# Proiect.net
KiCad netlist of a schematic drawn in EAGLE
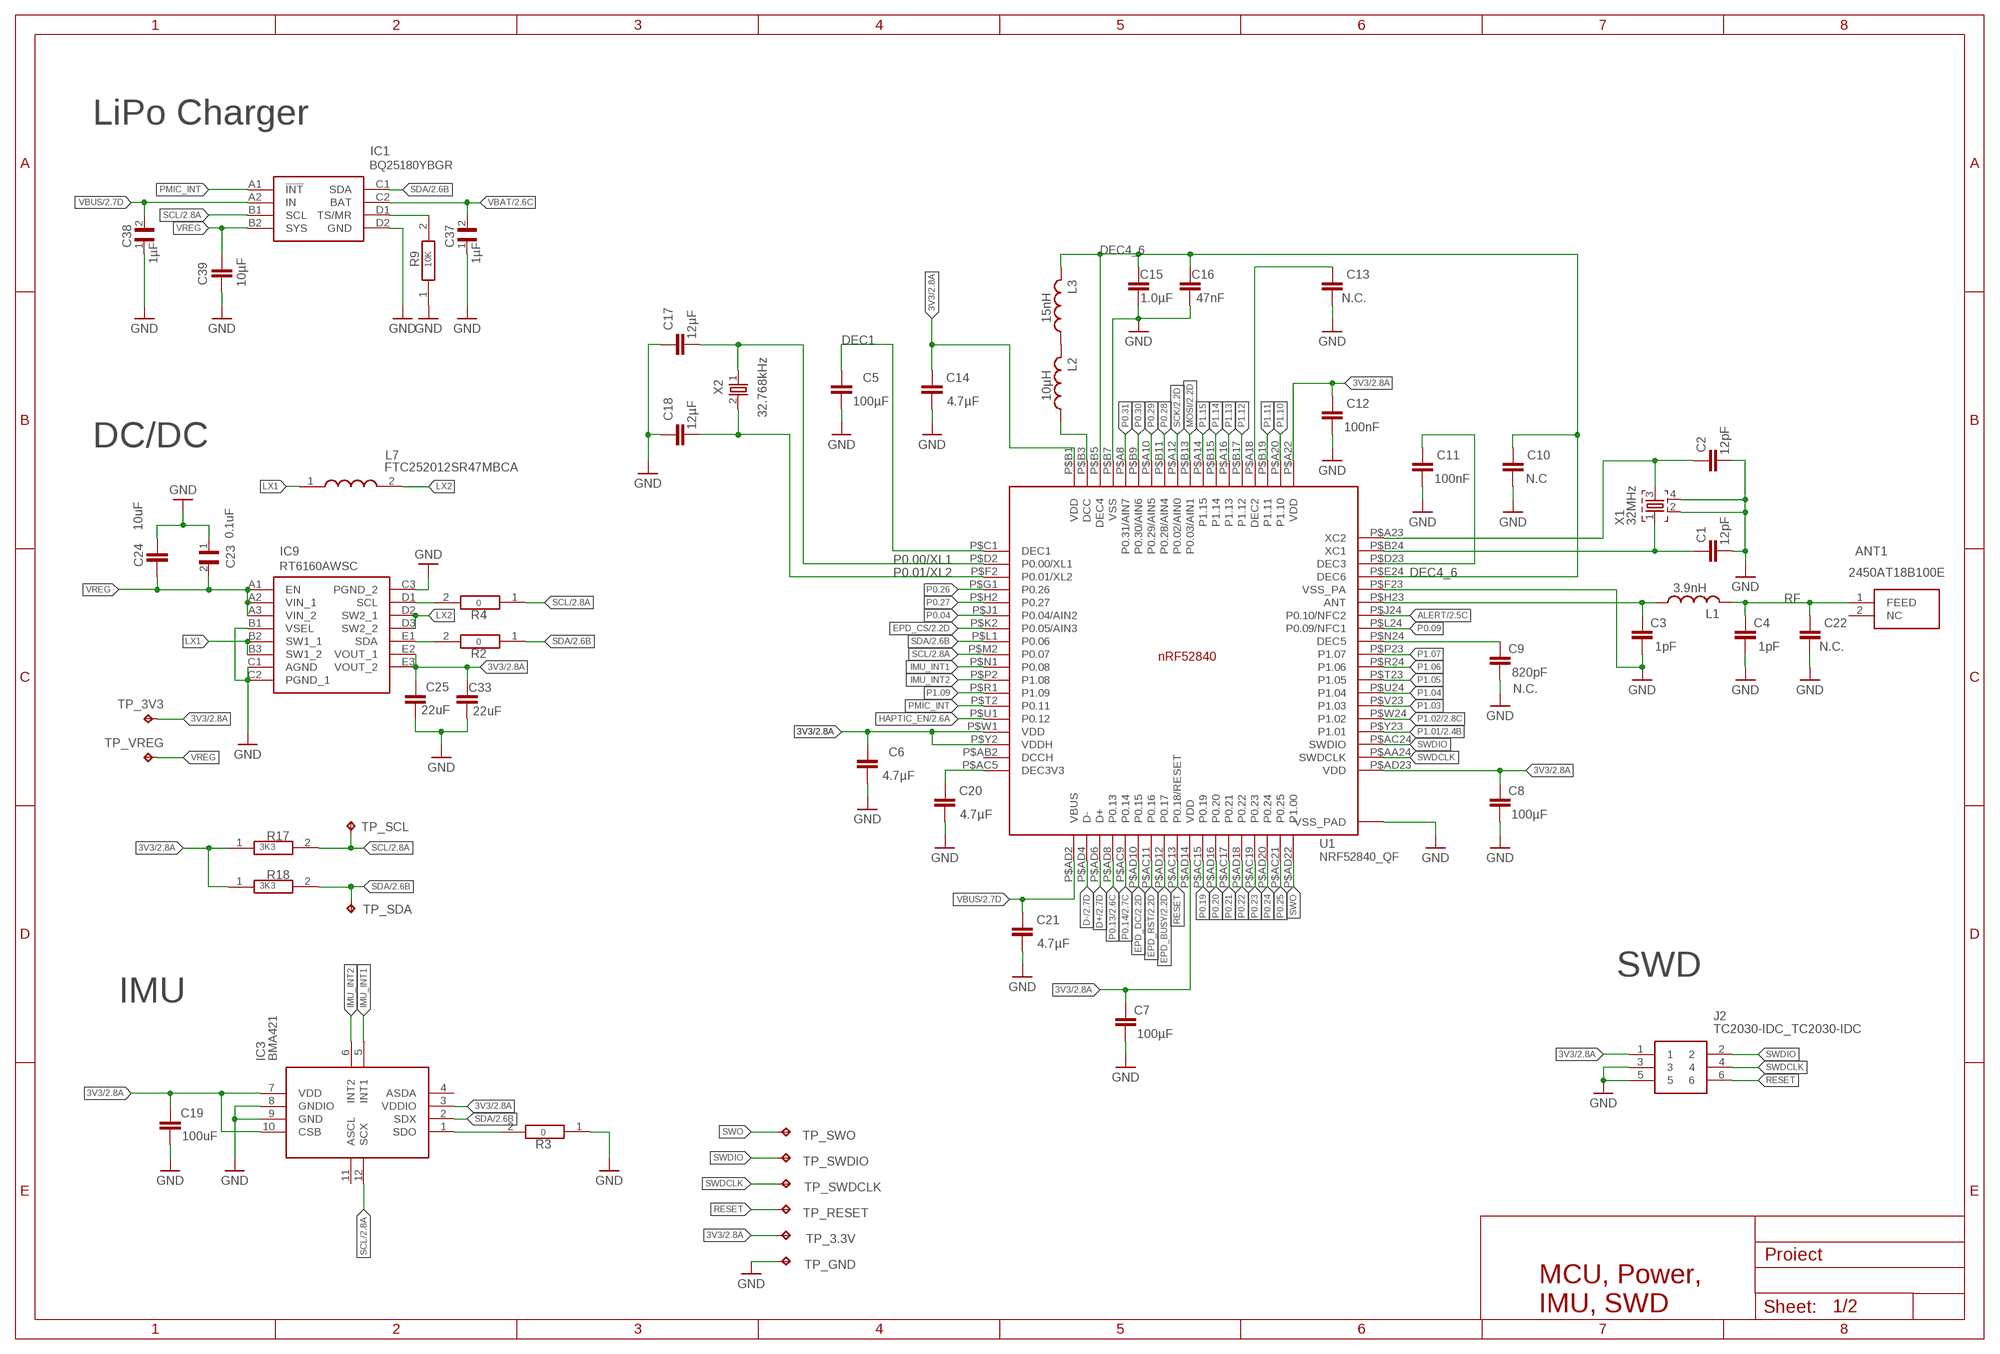
[diagram p0: schematic, sheet 1]
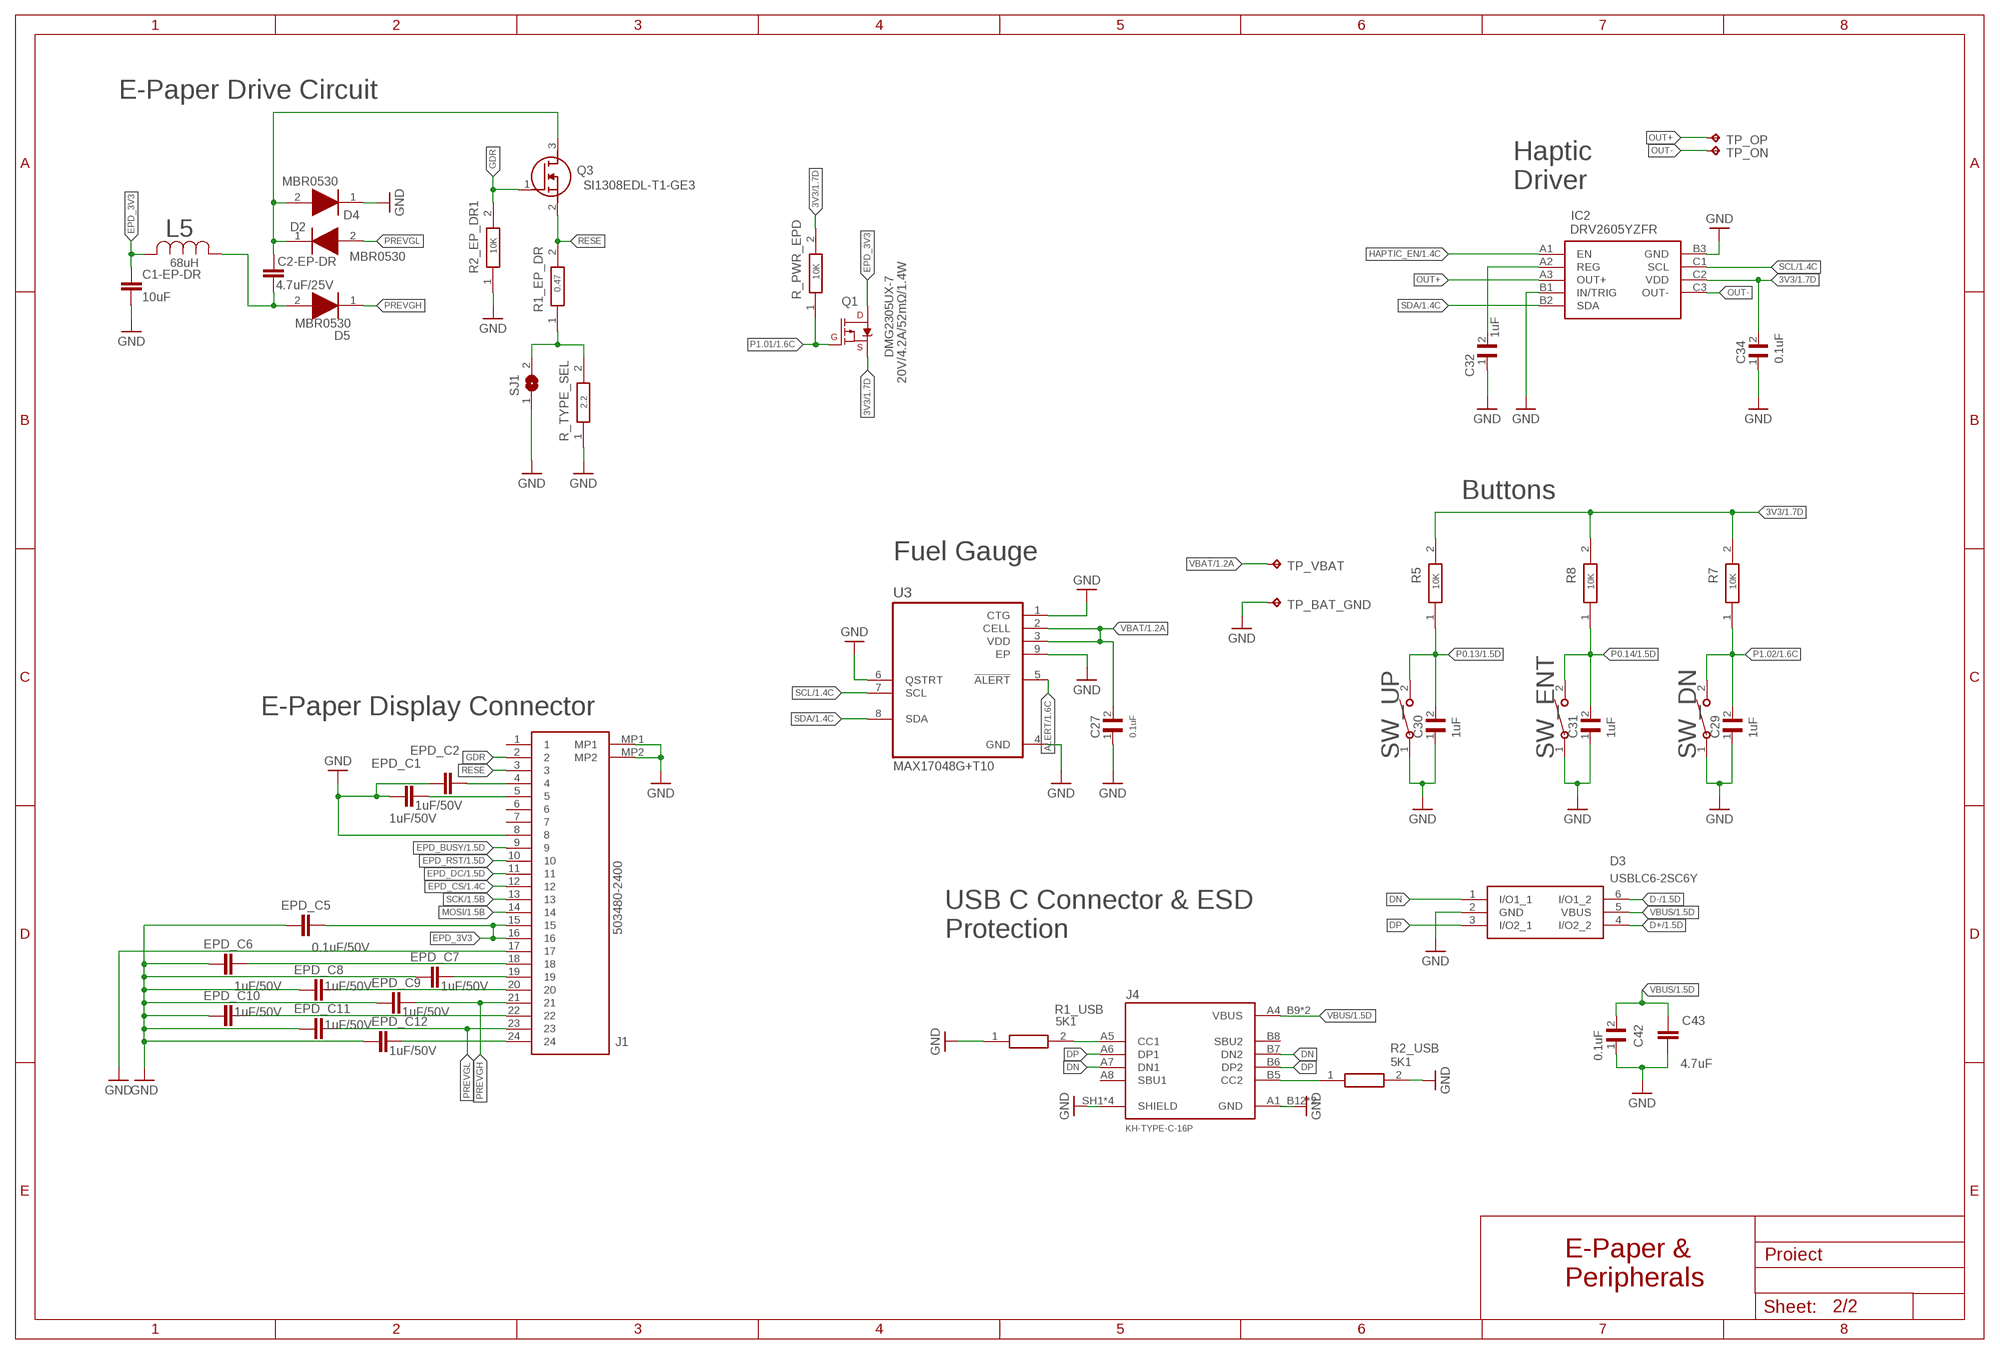
[diagram p1: schematic, sheet 2]

(export (version "E")
  (design (tool "Eeschema 10.0.6"))
  (components
    (comp (ref "C1-EP-DR")
      (value "10uF")
      (footprint "eagle-import:NORDIC_NRF_3_RESC0201_L")
      (libsource (lib "eagle-import") (part "NORDIC_NRF_3_CAPACITOR_0201_L"))
    )
    (comp (ref "C2-EP-DR")
      (value "4.7uF/25V")
      (footprint "eagle-import:NORDIC_NRF_3_RESC0201_L")
      (libsource (lib "eagle-import") (part "NORDIC_NRF_3_CAPACITOR_0201_L"))
    )
    (comp (ref "C27")
      (value "GRM011R60J152KE01L_2_GRM011R60J152KE01L")
      (footprint "eagle-import:GRM011R60J152KE01L_2_CAPC0201X13N")
      (fields
        (field (name "MF") "Murata")
        (field (name "MP") "GRM011R60J152KE01L")
        (field (name "F") "0.1uF")
      )
      (libsource (lib "eagle-import") (part "GRM011R60J152KE01L_2_GRM011R60J152KE01L"))
    )
    (comp (ref "C29")
      (value "GRM011R60J152KE01L_2_GRM011R60J152KE01L")
      (footprint "eagle-import:GRM011R60J152KE01L_2_CAPC0201X13N")
      (fields (field (name "MF") "Murata") (field (name "MP") "GRM011R60J152KE01L") (field (name "F") "1uF"))
      (libsource (lib "eagle-import") (part "GRM011R60J152KE01L_2_GRM011R60J152KE01L"))
    )
    (comp (ref "C30")
      (value "GRM011R60J152KE01L_2_GRM011R60J152KE01L")
      (footprint "eagle-import:GRM011R60J152KE01L_2_CAPC0201X13N")
      (fields (field (name "MF") "Murata") (field (name "MP") "GRM011R60J152KE01L") (field (name "F") "1uF"))
      (libsource (lib "eagle-import") (part "GRM011R60J152KE01L_2_GRM011R60J152KE01L"))
    )
    (comp (ref "C31")
      (value "GRM011R60J152KE01L_2_GRM011R60J152KE01L")
      (footprint "eagle-import:GRM011R60J152KE01L_2_CAPC0201X13N")
      (fields (field (name "MF") "Murata") (field (name "MP") "GRM011R60J152KE01L") (field (name "F") "1uF"))
      (libsource (lib "eagle-import") (part "GRM011R60J152KE01L_2_GRM011R60J152KE01L"))
    )
    (comp (ref "C32")
      (value "GRM011R60J152KE01L_2_GRM011R60J152KE01L")
      (footprint "eagle-import:GRM011R60J152KE01L_2_CAPC0201X13N")
      (fields (field (name "MF") "Murata") (field (name "MP") "GRM011R60J152KE01L") (field (name "F") "1uF"))
      (libsource (lib "eagle-import") (part "GRM011R60J152KE01L_2_GRM011R60J152KE01L"))
    )
    (comp (ref "C34")
      (value "GRM011R60J152KE01L_2_GRM011R60J152KE01L")
      (footprint "eagle-import:GRM011R60J152KE01L_2_CAPC0201X13N")
      (fields
        (field (name "MF") "Murata")
        (field (name "MP") "GRM011R60J152KE01L")
        (field (name "F") "0.1uF")
      )
      (libsource (lib "eagle-import") (part "GRM011R60J152KE01L_2_GRM011R60J152KE01L"))
    )
    (comp (ref "C42")
      (value "GRM011R60J152KE01L_2_GRM011R60J152KE01L")
      (footprint "eagle-import:GRM011R60J152KE01L_2_CAPC0201X13N")
      (fields
        (field (name "MF") "Murata")
        (field (name "MP") "GRM011R60J152KE01L")
        (field (name "F") "0.1uF")
      )
      (libsource (lib "eagle-import") (part "GRM011R60J152KE01L_2_GRM011R60J152KE01L"))
    )
    (comp (ref "C43")
      (value "4.7uF")
      (footprint "eagle-import:NORDIC_NRF_3_RESC0201_L")
      (libsource (lib "eagle-import") (part "NORDIC_NRF_3_CAPACITOR_0201_L"))
    )
    (comp (ref "D2")
      (value "ESP32_C6_LIBRARY_5_MBR0530")
      (footprint "eagle-import:ESP32_C6_LIBRARY_5_SOD3716X135N")
      (fields (field (name "MF") "ON Semiconductor") (field (name "MP") "MBR0530"))
      (libsource (lib "eagle-import") (part "ESP32_C6_LIBRARY_5_MBR0530"))
    )
    (comp (ref "D3")
      (value "ESP32_C6_LIBRARY_3_USBLC6-2SC6Y")
      (footprint "eagle-import:ESP32_C6_LIBRARY_3_SOT95P280X145-6N")
      (fields (field (name "MF") "STMicroelectronics") (field (name "MP") "USBLC6-2SC6Y"))
      (libsource (lib "eagle-import") (part "ESP32_C6_LIBRARY_3_USBLC6-2SC6Y"))
    )
    (comp (ref "D4")
      (value "ESP32_C6_LIBRARY_5_MBR0530")
      (footprint "eagle-import:ESP32_C6_LIBRARY_5_SOD3716X135N")
      (fields (field (name "MF") "ON Semiconductor") (field (name "MP") "MBR0530"))
      (libsource (lib "eagle-import") (part "ESP32_C6_LIBRARY_5_MBR0530"))
    )
    (comp (ref "D5")
      (value "ESP32_C6_LIBRARY_5_MBR0530")
      (footprint "eagle-import:ESP32_C6_LIBRARY_5_SOD3716X135N")
      (fields (field (name "MF") "ON Semiconductor") (field (name "MP") "MBR0530"))
      (libsource (lib "eagle-import") (part "ESP32_C6_LIBRARY_5_MBR0530"))
    )
    (comp (ref "EPD_C1")
      (value "1uF/50V")
      (footprint "eagle-import:NORDIC_NRF_3_RESC0201_L")
      (libsource (lib "eagle-import") (part "NORDIC_NRF_3_CAPACITOR_0201_L"))
    )
    (comp (ref "EPD_C2")
      (value "1uF/50V")
      (footprint "eagle-import:NORDIC_NRF_3_RESC0201_L")
      (libsource (lib "eagle-import") (part "NORDIC_NRF_3_CAPACITOR_0201_L"))
    )
    (comp (ref "EPD_C5")
      (value "0.1uF/50V")
      (footprint "eagle-import:NORDIC_NRF_3_RESC0201_L")
      (libsource (lib "eagle-import") (part "NORDIC_NRF_3_CAPACITOR_0201_L"))
    )
    (comp (ref "EPD_C6")
      (value "1uF/50V")
      (footprint "eagle-import:NORDIC_NRF_3_RESC0201_L")
      (libsource (lib "eagle-import") (part "NORDIC_NRF_3_CAPACITOR_0201_L"))
    )
    (comp (ref "EPD_C7")
      (value "1uF/50V")
      (footprint "eagle-import:NORDIC_NRF_3_RESC0201_L")
      (libsource (lib "eagle-import") (part "NORDIC_NRF_3_CAPACITOR_0201_L"))
    )
    (comp (ref "EPD_C8")
      (value "1uF/50V")
      (footprint "eagle-import:NORDIC_NRF_3_RESC0201_L")
      (libsource (lib "eagle-import") (part "NORDIC_NRF_3_CAPACITOR_0201_L"))
    )
    (comp (ref "EPD_C9")
      (value "1uF/50V")
      (footprint "eagle-import:NORDIC_NRF_3_RESC0201_L")
      (libsource (lib "eagle-import") (part "NORDIC_NRF_3_CAPACITOR_0201_L"))
    )
    (comp (ref "EPD_C10")
      (value "1uF/50V")
      (footprint "eagle-import:NORDIC_NRF_3_RESC0201_L")
      (libsource (lib "eagle-import") (part "NORDIC_NRF_3_CAPACITOR_0201_L"))
    )
    (comp (ref "EPD_C11")
      (value "1uF/50V")
      (footprint "eagle-import:NORDIC_NRF_3_RESC0201_L")
      (libsource (lib "eagle-import") (part "NORDIC_NRF_3_CAPACITOR_0201_L"))
    )
    (comp (ref "EPD_C12")
      (value "1uF/50V")
      (footprint "eagle-import:NORDIC_NRF_3_RESC0201_L")
      (libsource (lib "eagle-import") (part "NORDIC_NRF_3_CAPACITOR_0201_L"))
    )
    (comp (ref "IC2")
      (value "DRV2605YZFR_DRV2605YZFR")
      (footprint "eagle-import:DRV2605YZFR_BGA9C50P3X3_144X144X62")
      (fields
        (field (name "ARROW_PART_NUMBER") "DRV2605YZFR")
        (field (name "MANUFACTURER_PART_NUMBER") "DRV2605YZFR")
      )
      (libsource (lib "eagle-import") (part "DRV2605YZFR_DRV2605YZFR"))
    )
    (comp (ref "J1")
      (value "503480-2400_503480-2400")
      (footprint "eagle-import:503480-2400_5034802400")
      (fields
        (field (name "MANUFACTURER_PART_NUMBER") "503480-2400")
        (field (name "MOUSER_PART_NUMBER") "538-503480-2400")
      )
      (libsource (lib "eagle-import") (part "503480-2400_503480-2400"))
    )
    (comp (ref "J4")
      (value "KH-TYPE-C-16P_KH-TYPE-C-16P")
      (footprint "eagle-import:KH-TYPE-C-16P_KINGHELM_KH-TYPE-C-16P")
      (fields (field (name "MF") "kinghelm") (field (name "MP") "KH-TYPE-C-16P"))
      (libsource (lib "eagle-import") (part "KH-TYPE-C-16P_KH-TYPE-C-16P"))
    )
    (comp (ref "L5")
      (value "ESP32_C6_LIBRARY_2_744043680IND_4828-WE-TPC_WRE")
      (footprint "eagle-import:ESP32_C6_LIBRARY_2_IND_4828-WE-TPC_WRE")
      (fields
        (field (name "MANUFACTURER_PART_NUMBER") "744043680")
        (field (name "ATR") "68uH")
        (field (name "COPYRIGHT") "Copyright (C) 2024 Ultra Librarian. All rights reserved.")
      )
      (libsource (lib "eagle-import") (part "ESP32_C6_LIBRARY_2_744043680IND_4828-WE-TPC_WRE"))
    )
    (comp (ref "Q1")
      (value "20V/4.2A/52mΩ/1.4W")
      (footprint "eagle-import:ESP32_C6_LIBRARY_4_ESP32_C6_LIBRARY_4_ESP32_C6_LIBRARY_4_ESP32_C6_LIBRARY_4_ESP32_WROVER_SPARKFUN-DISCRETESEMI_SOT23-3")
      (fields (field (name "NAM") "DMG2305UX-7 "))
      (libsource (lib "eagle-import") (part "ESP32_C6_LIBRARY_4_ESP32_WROVER_SPARKFUN-DISCRETESEMI_MOSFET_PCH-DMG2305UX-7"))
    )
    (comp (ref "Q3")
      (value "ESP32_C6_LIBRARY_6_SI1308EDL-T1-GE3")
      (footprint "eagle-import:ESP32_C6_LIBRARY_6_SOT65P210X110-3N")
      (fields (field (name "MF") "Vishay Siliconix") (field (name "MP") "SI1308EDL-T1-GE3"))
      (libsource (lib "eagle-import") (part "ESP32_C6_LIBRARY_6_SI1308EDL-T1-GE3"))
    )
    (comp (ref "R1_EP_DR")
      (value "ERA-1AEB3401C_CPF0201D7K68C1")
      (footprint "eagle-import:ERA-1AEB3401C_0201")
      (fields (field (name "ATR") "0.47"))
      (libsource (lib "eagle-import") (part "ERA-1AEB3401C_CPF0201D7K68C1"))
    )
    (comp (ref "R1_USB")
      (value "ERA-1AEB3401C_CPF0201D7K68C1")
      (footprint "eagle-import:ERA-1AEB3401C_0201")
      (fields (field (name "ATR") "5K1"))
      (libsource (lib "eagle-import") (part "ERA-1AEB3401C_CPF0201D7K68C1"))
    )
    (comp (ref "R2_EP_DR1")
      (value "ERA-1AEB3401C_CPF0201D7K68C1")
      (footprint "eagle-import:ERA-1AEB3401C_0201")
      (fields (field (name "ATR") "10K"))
      (libsource (lib "eagle-import") (part "ERA-1AEB3401C_CPF0201D7K68C1"))
    )
    (comp (ref "R2_USB")
      (value "ERA-1AEB3401C_CPF0201D7K68C1")
      (footprint "eagle-import:ERA-1AEB3401C_0201")
      (fields (field (name "ATR") "5K1"))
      (libsource (lib "eagle-import") (part "ERA-1AEB3401C_CPF0201D7K68C1"))
    )
    (comp (ref "R5")
      (value "ERA-1AEB3401C_CPF0201D7K68C1")
      (footprint "eagle-import:ERA-1AEB3401C_0201")
      (fields (field (name "ATR") "10K"))
      (libsource (lib "eagle-import") (part "ERA-1AEB3401C_CPF0201D7K68C1"))
    )
    (comp (ref "R7")
      (value "ERA-1AEB3401C_CPF0201D7K68C1")
      (footprint "eagle-import:ERA-1AEB3401C_0201")
      (fields (field (name "ATR") "10K"))
      (libsource (lib "eagle-import") (part "ERA-1AEB3401C_CPF0201D7K68C1"))
    )
    (comp (ref "R8")
      (value "ERA-1AEB3401C_CPF0201D7K68C1")
      (footprint "eagle-import:ERA-1AEB3401C_0201")
      (fields (field (name "ATR") "10K"))
      (libsource (lib "eagle-import") (part "ERA-1AEB3401C_CPF0201D7K68C1"))
    )
    (comp (ref "R_PWR_EPD")
      (value "ERA-1AEB3401C_CPF0201D7K68C1")
      (footprint "eagle-import:ERA-1AEB3401C_0201")
      (fields (field (name "ATR") "10K"))
      (libsource (lib "eagle-import") (part "ERA-1AEB3401C_CPF0201D7K68C1"))
    )
    (comp (ref "R_TYPE_SEL")
      (value "ERA-1AEB3401C_CPF0201D7K68C1")
      (footprint "eagle-import:ERA-1AEB3401C_0201")
      (fields (field (name "ATR") "2.2"))
      (libsource (lib "eagle-import") (part "ERA-1AEB3401C_CPF0201D7K68C1"))
    )
    (comp (ref "SJ1")
      (value "ESP32_C6_LIBRARY_7_JUMPER_SJ")
      (footprint "eagle-import:ESP32_C6_LIBRARY_7_JUMPER_SJ")
      (libsource (lib "eagle-import") (part "ESP32_C6_LIBRARY_7_JUMPER_SJ"))
    )
    (comp (ref "SW_DN")
      (value "2025-10-22_07-23-44_LIBRARY_EVP-AKE31ASW_EVP-AKE31A_PAN")
      (footprint "eagle-import:2025-10-22_07-23-44_LIBRARY_SW_EVP-AKE31A_PAN")
      (fields
        (field (name "MANUFACTURER_PART_NUMBER") "EVP-AKE31A")
        (field (name "COPYRIGHT") "Copyright (C) 2025 Ultra Librarian. All rights reserved.")
      )
      (libsource (lib "eagle-import") (part "2025-10-22_07-23-44_LIBRARY_EVP-AKE31ASW_EVP-AKE31A_PAN"))
    )
    (comp (ref "SW_ENT")
      (value "2025-10-22_07-23-44_LIBRARY_EVP-AKE31ASW_EVP-AKE31A_PAN")
      (footprint "eagle-import:2025-10-22_07-23-44_LIBRARY_SW_EVP-AKE31A_PAN")
      (fields
        (field (name "MANUFACTURER_PART_NUMBER") "EVP-AKE31A")
        (field (name "COPYRIGHT") "Copyright (C) 2025 Ultra Librarian. All rights reserved.")
      )
      (libsource (lib "eagle-import") (part "2025-10-22_07-23-44_LIBRARY_EVP-AKE31ASW_EVP-AKE31A_PAN"))
    )
    (comp (ref "SW_UP")
      (value "2025-10-22_07-23-44_LIBRARY_EVP-AKE31ASW_EVP-AKE31A_PAN")
      (footprint "eagle-import:2025-10-22_07-23-44_LIBRARY_SW_EVP-AKE31A_PAN")
      (fields
        (field (name "MANUFACTURER_PART_NUMBER") "EVP-AKE31A")
        (field (name "COPYRIGHT") "Copyright (C) 2025 Ultra Librarian. All rights reserved.")
      )
      (libsource (lib "eagle-import") (part "2025-10-22_07-23-44_LIBRARY_EVP-AKE31ASW_EVP-AKE31A_PAN"))
    )
    (comp (ref "TP_BAT_GND")
      (value "HECTOR_WATCH_1_TPTP20R")
      (footprint "eagle-import:HECTOR_WATCH_1_TP20R")
      (libsource (lib "eagle-import") (part "HECTOR_WATCH_1_TPTP20R"))
    )
    (comp (ref "TP_ON")
      (value "HECTOR_WATCH_1_TPTP20R")
      (footprint "eagle-import:HECTOR_WATCH_1_TP20R")
      (libsource (lib "eagle-import") (part "HECTOR_WATCH_1_TPTP20R"))
    )
    (comp (ref "TP_OP")
      (value "HECTOR_WATCH_1_TPTP20R")
      (footprint "eagle-import:HECTOR_WATCH_1_TP20R")
      (libsource (lib "eagle-import") (part "HECTOR_WATCH_1_TPTP20R"))
    )
    (comp (ref "TP_VBAT")
      (value "HECTOR_WATCH_1_TPTP20R")
      (footprint "eagle-import:HECTOR_WATCH_1_TP20R")
      (libsource (lib "eagle-import") (part "HECTOR_WATCH_1_TPTP20R"))
    )
    (comp (ref "U3")
      (value "ESP32_C6_LIBRARY_MAX17048G+T10")
      (footprint "eagle-import:ESP32_C6_LIBRARY_SON50P200X200X80-9N")
      (fields (field (name "MF") "Analog Devices") (field (name "MP") "MAX17048G+T10"))
      (libsource (lib "eagle-import") (part "ESP32_C6_LIBRARY_MAX17048G+T10"))
    )
    (comp (ref "ANT1")
      (value "2450AT18B100E_2450AT18B100E")
      (footprint "eagle-import:2450AT18B100E_ANTC3216X140N")
      (fields
        (field (name "ARROW_PART_NUMBER") "2450AT18B100E")
        (field (name "MANUFACTURER_PART_NUMBER") "2450AT18B100E")
        (field (name "MOUSER_PART_NUMBER") "609-2450AT18B100E")
      )
      (libsource (lib "eagle-import") (part "2450AT18B100E_2450AT18B100E"))
    )
    (comp (ref "C1")
      (value "12pF")
      (footprint "eagle-import:NORDIC_NRF_3_RESC0201_L")
      (libsource (lib "eagle-import") (part "NORDIC_NRF_3_CAPACITOR_0201_L"))
    )
    (comp (ref "C2")
      (value "12pF")
      (footprint "eagle-import:NORDIC_NRF_3_RESC0201_L")
      (libsource (lib "eagle-import") (part "NORDIC_NRF_3_CAPACITOR_0201_L"))
    )
    (comp (ref "C3")
      (value "1pF")
      (footprint "eagle-import:NORDIC_NRF_3_RESC0201_L")
      (libsource (lib "eagle-import") (part "NORDIC_NRF_3_CAPACITOR_0201_L"))
    )
    (comp (ref "C4")
      (value "1pF")
      (footprint "eagle-import:NORDIC_NRF_3_RESC0201_L")
      (libsource (lib "eagle-import") (part "NORDIC_NRF_3_CAPACITOR_0201_L"))
    )
    (comp (ref "C5")
      (value "100µF")
      (footprint "eagle-import:NORDIC_NRF_3_RESC0201_L")
      (libsource (lib "eagle-import") (part "NORDIC_NRF_3_CAPACITOR_0201_L"))
    )
    (comp (ref "C6")
      (value "4.7µF")
      (footprint "eagle-import:NORDIC_NRF_3_RESC0201_L")
      (libsource (lib "eagle-import") (part "NORDIC_NRF_3_CAPACITOR_0201_L"))
    )
    (comp (ref "C7")
      (value "100µF")
      (footprint "eagle-import:NORDIC_NRF_3_RESC0201_L")
      (libsource (lib "eagle-import") (part "NORDIC_NRF_3_CAPACITOR_0201_L"))
    )
    (comp (ref "C8")
      (value "100µF")
      (footprint "eagle-import:NORDIC_NRF_3_RESC0201_L")
      (libsource (lib "eagle-import") (part "NORDIC_NRF_3_CAPACITOR_0201_L"))
    )
    (comp (ref "C9")
      (value "820pF")
      (footprint "eagle-import:NORDIC_NRF_3_RESC0201_L")
      (fields (field (name "NO") "N.C."))
      (libsource (lib "eagle-import") (part "NORDIC_NRF_3_CAPACITOR_0201_L"))
    )
    (comp (ref "C10")
      (value "N.C")
      (footprint "eagle-import:NORDIC_NRF_3_RESC0201_L")
      (libsource (lib "eagle-import") (part "NORDIC_NRF_3_CAPACITOR_0201_L"))
    )
    (comp (ref "C11")
      (value "100nF")
      (footprint "eagle-import:NORDIC_NRF_3_RESC0201_L")
      (libsource (lib "eagle-import") (part "NORDIC_NRF_3_CAPACITOR_0201_L"))
    )
    (comp (ref "C12")
      (value "100nF")
      (footprint "eagle-import:NORDIC_NRF_3_RESC0201_L")
      (libsource (lib "eagle-import") (part "NORDIC_NRF_3_CAPACITOR_0201_L"))
    )
    (comp (ref "C13")
      (value "N.C.")
      (footprint "eagle-import:NORDIC_NRF_3_RESC0201_L")
      (libsource (lib "eagle-import") (part "NORDIC_NRF_3_CAPACITOR_0201_L"))
    )
    (comp (ref "C14")
      (value "4.7µF")
      (footprint "eagle-import:NORDIC_NRF_3_RESC0201_L")
      (libsource (lib "eagle-import") (part "NORDIC_NRF_3_CAPACITOR_0201_L"))
    )
    (comp (ref "C15")
      (value "1.0µF")
      (footprint "eagle-import:NORDIC_NRF_3_RESC0201_L")
      (libsource (lib "eagle-import") (part "NORDIC_NRF_3_CAPACITOR_0201_L"))
    )
    (comp (ref "C16")
      (value "47nF")
      (footprint "eagle-import:NORDIC_NRF_3_RESC0201_L")
      (libsource (lib "eagle-import") (part "NORDIC_NRF_3_CAPACITOR_0201_L"))
    )
    (comp (ref "C17")
      (value "12µF")
      (footprint "eagle-import:NORDIC_NRF_3_RESC0201_L")
      (libsource (lib "eagle-import") (part "NORDIC_NRF_3_CAPACITOR_0201_L"))
    )
    (comp (ref "C18")
      (value "12µF")
      (footprint "eagle-import:NORDIC_NRF_3_RESC0201_L")
      (libsource (lib "eagle-import") (part "NORDIC_NRF_3_CAPACITOR_0201_L"))
    )
    (comp (ref "C19")
      (value "100uF")
      (footprint "eagle-import:NORDIC_NRF_3_RESC0201_L")
      (libsource (lib "eagle-import") (part "NORDIC_NRF_3_CAPACITOR_0201_L"))
    )
    (comp (ref "C20")
      (value "4.7µF")
      (footprint "eagle-import:NORDIC_NRF_3_RESC0201_L")
      (libsource (lib "eagle-import") (part "NORDIC_NRF_3_CAPACITOR_0201_L"))
    )
    (comp (ref "C21")
      (value "4.7µF")
      (footprint "eagle-import:NORDIC_NRF_3_RESC0201_L")
      (libsource (lib "eagle-import") (part "NORDIC_NRF_3_CAPACITOR_0201_L"))
    )
    (comp (ref "C22")
      (value "N.C.")
      (footprint "eagle-import:NORDIC_NRF_3_RESC0201_L")
      (libsource (lib "eagle-import") (part "NORDIC_NRF_3_CAPACITOR_0201_L"))
    )
    (comp (ref "C23")
      (value "GRM011R60J152KE01L_2_GRM011R60J152KE01L")
      (footprint "eagle-import:GRM011R60J152KE01L_2_CAPC0201X13N")
      (fields
        (field (name "MF") "Murata")
        (field (name "MP") "GRM011R60J152KE01L")
        (field (name "F") "0.1uF")
      )
      (libsource (lib "eagle-import") (part "GRM011R60J152KE01L_2_GRM011R60J152KE01L"))
    )
    (comp (ref "C24")
      (value "10uF")
      (footprint "eagle-import:NORDIC_NRF_3_RESC0201_L")
      (libsource (lib "eagle-import") (part "NORDIC_NRF_3_CAPACITOR_0201_L"))
    )
    (comp (ref "C25")
      (value "22uF")
      (footprint "eagle-import:NORDIC_NRF_3_RESC0201_L")
      (libsource (lib "eagle-import") (part "NORDIC_NRF_3_CAPACITOR_0201_L"))
    )
    (comp (ref "C33")
      (value "22uF")
      (footprint "eagle-import:NORDIC_NRF_3_RESC0201_L")
      (libsource (lib "eagle-import") (part "NORDIC_NRF_3_CAPACITOR_0201_L"))
    )
    (comp (ref "C37")
      (value "GRM011R60J152KE01L_2_GRM011R60J152KE01L")
      (footprint "eagle-import:GRM011R60J152KE01L_2_CAPC0201X13N")
      (fields (field (name "MF") "Murata") (field (name "MP") "GRM011R60J152KE01L") (field (name "F") "1µF"))
      (libsource (lib "eagle-import") (part "GRM011R60J152KE01L_2_GRM011R60J152KE01L"))
    )
    (comp (ref "C38")
      (value "GRM011R60J152KE01L_2_GRM011R60J152KE01L")
      (footprint "eagle-import:GRM011R60J152KE01L_2_CAPC0201X13N")
      (fields (field (name "MF") "Murata") (field (name "MP") "GRM011R60J152KE01L") (field (name "F") "1µF"))
      (libsource (lib "eagle-import") (part "GRM011R60J152KE01L_2_GRM011R60J152KE01L"))
    )
    (comp (ref "C39")
      (value "10µF")
      (footprint "eagle-import:NORDIC_NRF_3_RESC0201_L")
      (libsource (lib "eagle-import") (part "NORDIC_NRF_3_CAPACITOR_0201_L"))
    )
    (comp (ref "IC1")
      (value "BQ25180YBGR_BQ25180YBGR")
      (footprint "eagle-import:BQ25180YBGR_BGA8C40P2X4_100X155X50")
      (fields
        (field (name "ARROW_PART_NUMBER") "BQ25180YBGR")
        (field (name "MANUFACTURER_PART_NUMBER") "BQ25180YBGR")
        (field (name "MOUSER_PART_NUMBER") "595-BQ25180YBGR")
      )
      (libsource (lib "eagle-import") (part "BQ25180YBGR_BQ25180YBGR"))
    )
    (comp (ref "IC3")
      (value "BMA423_BMA423")
      (footprint "eagle-import:BMA423_BMA423")
      (fields
        (field (name "ARROW_PART_NUMBER") "BMA423")
        (field (name "MANUFACTURER_PART_NUMBER") "BMA423")
        (field (name "MOUSER_PART_NUMBER") "262-BMA423")
        (field (name "ARROW_PART_NUMBER_1") "BMA421")
      )
      (libsource (lib "eagle-import") (part "BMA423_BMA423"))
    )
    (comp (ref "IC9")
      (value "RT6160AWSC_RT6160AWSC")
      (footprint "eagle-import:RT6160AWSC_BGA15C40P3X5_140X230X60")
      (fields
        (field (name "MANUFACTURER_PART_NUMBER") "RT6160AWSC")
        (field (name "MOUSER_PART_NUMBER") "835-RT6160AWSC")
      )
      (libsource (lib "eagle-import") (part "RT6160AWSC_RT6160AWSC"))
    )
    (comp (ref "J2")
      (value "TC2030-IDC_TC2030-IDC")
      (footprint "eagle-import:TC2030-IDC_TC2030IDC")
      (fields (field (name "MANUFACTURER_PART_NUMBER") "TC2030-IDC"))
      (libsource (lib "eagle-import") (part "TC2030-IDC_TC2030-IDC"))
    )
    (comp (ref "L1")
      (value "3.9nH")
      (footprint "eagle-import:NORDIC_NRF_2_RESC0402_L")
      (libsource (lib "eagle-import") (part "NORDIC_NRF_2_INDUCTOR_0402_L"))
    )
    (comp (ref "L2")
      (value "10µH")
      (footprint "eagle-import:NORDIC_NRF_2_RESC0402_L")
      (libsource (lib "eagle-import") (part "NORDIC_NRF_2_INDUCTOR_0402_L"))
    )
    (comp (ref "L3")
      (value "15nH")
      (footprint "eagle-import:NORDIC_NRF_2_RESC0402_L")
      (libsource (lib "eagle-import") (part "NORDIC_NRF_2_INDUCTOR_0402_L"))
    )
    (comp (ref "L7")
      (value "MLP2016SR47MT0S1_FTC252012SR47MBCA")
      (footprint "eagle-import:MLP2016SR47MT0S1_INDC2016X100N")
      (fields
        (field (name "MANUFACTURER_PART_NUMBER") "FTC252012SR47MBCA")
        (field (name "N") "FTC252012SR47MBCA")
      )
      (libsource (lib "eagle-import") (part "MLP2016SR47MT0S1_FTC252012SR47MBCA"))
    )
    (comp (ref "R2")
      (value "ERA-1AEB3401C_CPF0201D7K68C1")
      (footprint "eagle-import:ERA-1AEB3401C_0201")
      (fields (field (name "R") "0"))
      (libsource (lib "eagle-import") (part "ERA-1AEB3401C_CPF0201D7K68C1"))
    )
    (comp (ref "R3")
      (value "ERA-1AEB3401C_CPF0201D7K68C1")
      (footprint "eagle-import:ERA-1AEB3401C_0201")
      (fields (field (name "R") "0"))
      (libsource (lib "eagle-import") (part "ERA-1AEB3401C_CPF0201D7K68C1"))
    )
    (comp (ref "R4")
      (value "ERA-1AEB3401C_CPF0201D7K68C1")
      (footprint "eagle-import:ERA-1AEB3401C_0201")
      (fields (field (name "R") "0"))
      (libsource (lib "eagle-import") (part "ERA-1AEB3401C_CPF0201D7K68C1"))
    )
    (comp (ref "R9")
      (value "ERA-1AEB3401C_CPF0201D7K68C1")
      (footprint "eagle-import:ERA-1AEB3401C_0201")
      (fields (field (name "R") "10K"))
      (libsource (lib "eagle-import") (part "ERA-1AEB3401C_CPF0201D7K68C1"))
    )
    (comp (ref "R17")
      (value "ERA-1AEB3401C_CPF0201D7K68C1")
      (footprint "eagle-import:ERA-1AEB3401C_0201")
      (fields (field (name "R") "3K3"))
      (libsource (lib "eagle-import") (part "ERA-1AEB3401C_CPF0201D7K68C1"))
    )
    (comp (ref "R18")
      (value "ERA-1AEB3401C_CPF0201D7K68C1")
      (footprint "eagle-import:ERA-1AEB3401C_0201")
      (fields (field (name "R") "3K3"))
      (libsource (lib "eagle-import") (part "ERA-1AEB3401C_CPF0201D7K68C1"))
    )
    (comp (ref "TP_3.3V")
      (value "HECTOR_WATCH_1_TPTP20R")
      (footprint "eagle-import:HECTOR_WATCH_1_TP20R")
      (libsource (lib "eagle-import") (part "HECTOR_WATCH_1_TPTP20R"))
    )
    (comp (ref "TP_3V3")
      (value "HECTOR_WATCH_1_TPTP20R")
      (footprint "eagle-import:HECTOR_WATCH_1_TP20R")
      (libsource (lib "eagle-import") (part "HECTOR_WATCH_1_TPTP20R"))
    )
    (comp (ref "TP_GND")
      (value "HECTOR_WATCH_1_TPTP20R")
      (footprint "eagle-import:HECTOR_WATCH_1_TP20R")
      (libsource (lib "eagle-import") (part "HECTOR_WATCH_1_TPTP20R"))
    )
    (comp (ref "TP_RESET")
      (value "HECTOR_WATCH_1_TPTP20R")
      (footprint "eagle-import:HECTOR_WATCH_1_TP20R")
      (libsource (lib "eagle-import") (part "HECTOR_WATCH_1_TPTP20R"))
    )
    (comp (ref "TP_SCL")
      (value "HECTOR_WATCH_1_TPTP20R")
      (footprint "eagle-import:HECTOR_WATCH_1_TP20R")
      (libsource (lib "eagle-import") (part "HECTOR_WATCH_1_TPTP20R"))
    )
    (comp (ref "TP_SDA")
      (value "HECTOR_WATCH_1_TPTP20R")
      (footprint "eagle-import:HECTOR_WATCH_1_TP20R")
      (libsource (lib "eagle-import") (part "HECTOR_WATCH_1_TPTP20R"))
    )
    (comp (ref "TP_SWDCLK")
      (value "HECTOR_WATCH_1_TPTP20R")
      (footprint "eagle-import:HECTOR_WATCH_1_TP20R")
      (libsource (lib "eagle-import") (part "HECTOR_WATCH_1_TPTP20R"))
    )
    (comp (ref "TP_SWDIO")
      (value "HECTOR_WATCH_1_TPTP20R")
      (footprint "eagle-import:HECTOR_WATCH_1_TP20R")
      (libsource (lib "eagle-import") (part "HECTOR_WATCH_1_TPTP20R"))
    )
    (comp (ref "TP_SWO")
      (value "HECTOR_WATCH_1_TPTP20R")
      (footprint "eagle-import:HECTOR_WATCH_1_TP20R")
      (libsource (lib "eagle-import") (part "HECTOR_WATCH_1_TPTP20R"))
    )
    (comp (ref "TP_VREG")
      (value "HECTOR_WATCH_1_TPTP20R")
      (footprint "eagle-import:HECTOR_WATCH_1_TP20R")
      (libsource (lib "eagle-import") (part "HECTOR_WATCH_1_TPTP20R"))
    )
    (comp (ref "U1")
      (value "NORDIC_NRF_4_NRF52840_QF")
      (footprint "eagle-import:NORDIC_NRF_4_AQFN50P700X700X85_HS-74N")
      (fields (field (name "NU") "NRF52840_QF"))
      (libsource (lib "eagle-import") (part "NORDIC_NRF_4_NRF52840_QF"))
    )
    (comp (ref "X1")
      (value "32MHz")
      (footprint "eagle-import:NORDIC_NRF_BT-XTAL_2016_N")
      (libsource (lib "eagle-import") (part "NORDIC_NRF_XTAL_32MHZ"))
    )
    (comp (ref "X2")
      (value "32.768kHz")
      (footprint "eagle-import:NORDIC_NRF_1_XTAL_3215_N")
      (libsource (lib "eagle-import") (part "NORDIC_NRF_1_XTAL_32KHZ"))
    )
  )
  (nets
    (net (code "1") (name "3V3") (class "Default")
      (node (ref "C12") (pin "1") (pinfunction "1_1") (pintype "passive"))
      (node (ref "C14") (pin "1") (pinfunction "1_1") (pintype "passive"))
      (node (ref "C19") (pin "1") (pinfunction "1_1") (pintype "passive"))
      (node (ref "C25") (pin "1") (pinfunction "1_1") (pintype "passive"))
      (node (ref "C33") (pin "1") (pinfunction "1_1") (pintype "passive"))
      (node (ref "C34") (pin "2") (pinfunction "2_2") (pintype "passive"))
      (node (ref "C6") (pin "1") (pinfunction "1_1") (pintype "passive"))
      (node (ref "C7") (pin "1") (pinfunction "1_1") (pintype "passive"))
      (node (ref "C8") (pin "1") (pinfunction "1_1") (pintype "passive"))
      (node (ref "IC2") (pin "C2") (pinfunction "VDD_C2") (pintype "bidirectional"))
      (node (ref "IC3") (pin "10") (pinfunction "CSB_10") (pintype "bidirectional"))
      (node (ref "IC3") (pin "3") (pinfunction "VDDIO_3") (pintype "bidirectional"))
      (node (ref "IC3") (pin "7") (pinfunction "VDD_7") (pintype "bidirectional"))
      (node (ref "IC9") (pin "E2") (pinfunction "VOUT_1_E2") (pintype "bidirectional"))
      (node (ref "IC9") (pin "E3") (pinfunction "VOUT_2_E3") (pintype "bidirectional"))
      (node (ref "J2") (pin "1") (pinfunction "1_1") (pintype "bidirectional"))
      (node (ref "Q1") (pin "2") (pinfunction "S_2") (pintype "bidirectional"))
      (node (ref "R17") (pin "1") (pinfunction "1_1") (pintype "bidirectional"))
      (node (ref "R18") (pin "1") (pinfunction "1_1") (pintype "bidirectional"))
      (node (ref "R_PWR_EPD") (pin "2") (pinfunction "2_2") (pintype "bidirectional"))
      (node (ref "TP_3.3V") (pin "TP") (pinfunction "TP_TP") (pintype "input"))
      (node (ref "TP_3V3") (pin "TP") (pinfunction "TP_TP") (pintype "input"))
      (node (ref "U1") (pin "P$A22") (pinfunction "VDD_P$A22") (pintype "power_in"))
      (node (ref "U1") (pin "P$AD14") (pinfunction "VDD_P$AD14") (pintype "power_in"))
      (node (ref "U1") (pin "P$AD23") (pinfunction "VDD_P$AD23") (pintype "power_in"))
      (node (ref "U1") (pin "P$B1") (pinfunction "VDD_P$B1") (pintype "power_in"))
      (node (ref "U1") (pin "P$W1") (pinfunction "VDD_P$W1") (pintype "power_in"))
      (node (ref "U1") (pin "P$Y2") (pinfunction "VDDH_P$Y2") (pintype "power_in"))
    )
    (net (code "2") (name "3V3{slash}1.7D") (class "Default")
      (node (ref "R5") (pin "2") (pinfunction "2_2") (pintype "bidirectional"))
      (node (ref "R7") (pin "2") (pinfunction "2_2") (pintype "bidirectional"))
      (node (ref "R8") (pin "2") (pinfunction "2_2") (pintype "bidirectional"))
    )
    (net (code "3") (name "ALERT") (class "Default")
      (node (ref "U1") (pin "P$J24") (pinfunction "P0.10/NFC2_P$J24") (pintype "bidirectional"))
      (node (ref "U3") (pin "5") (pinfunction "~{ALERT}_5") (pintype "output"))
    )
    (net (code "4") (name "D+") (class "Default")
      (node (ref "D3") (pin "4") (pinfunction "I/O2_2_4") (pintype "bidirectional"))
      (node (ref "U1") (pin "P$AD6") (pinfunction "D+_P$AD6") (pintype "bidirectional"))
    )
    (net (code "5") (name "D-") (class "Default")
      (node (ref "D3") (pin "6") (pinfunction "I/O1_2_6") (pintype "bidirectional"))
      (node (ref "U1") (pin "P$AD4") (pinfunction "D-_P$AD4") (pintype "bidirectional"))
    )
    (net (code "6") (name "DEC1") (class "Default")
      (node (ref "C5") (pin "1") (pinfunction "1_1") (pintype "passive"))
      (node (ref "U1") (pin "P$C1") (pinfunction "DEC1_P$C1") (pintype "power_in"))
    )
    (net (code "7") (name "DEC4_6") (class "Default")
      (node (ref "C10") (pin "1") (pinfunction "1_1") (pintype "passive"))
      (node (ref "C15") (pin "1") (pinfunction "1_1") (pintype "passive"))
      (node (ref "C16") (pin "1") (pinfunction "1_1") (pintype "passive"))
      (node (ref "L3") (pin "2") (pinfunction "2_2") (pintype "passive"))
      (node (ref "U1") (pin "P$B5") (pinfunction "DEC4_P$B5") (pintype "power_in"))
      (node (ref "U1") (pin "P$E24") (pinfunction "DEC6_P$E24") (pintype "bidirectional"))
    )
    (net (code "8") (name "DN") (class "Default")
      (node (ref "D3") (pin "1") (pinfunction "I/O1_1_1") (pintype "bidirectional"))
      (node (ref "J4") (pin "A7") (pinfunction "DN1_A7") (pintype "bidirectional"))
      (node (ref "J4") (pin "B7") (pinfunction "DN2_B7") (pintype "bidirectional"))
    )
    (net (code "9") (name "DP") (class "Default")
      (node (ref "D3") (pin "3") (pinfunction "I/O2_1_3") (pintype "bidirectional"))
      (node (ref "J4") (pin "A6") (pinfunction "DP1_A6") (pintype "bidirectional"))
      (node (ref "J4") (pin "B6") (pinfunction "DP2_B6") (pintype "bidirectional"))
    )
    (net (code "10") (name "EPD_3V3") (class "Default")
      (node (ref "C1-EP-DR") (pin "1") (pinfunction "1_1") (pintype "passive"))
      (node (ref "EPD_C5") (pin "2") (pinfunction "2_2") (pintype "passive"))
      (node (ref "J1") (pin "15") (pinfunction "15_15") (pintype "bidirectional"))
      (node (ref "J1") (pin "16") (pinfunction "16_16") (pintype "bidirectional"))
      (node (ref "L5") (pin "2") (pinfunction "2_2") (pintype "passive"))
      (node (ref "Q1") (pin "3") (pinfunction "D_3") (pintype "bidirectional"))
    )
    (net (code "11") (name "EPD_BUSY") (class "Default")
      (node (ref "J1") (pin "9") (pinfunction "9_9") (pintype "bidirectional"))
      (node (ref "U1") (pin "P$AD12") (pinfunction "P0.17_P$AD12") (pintype "bidirectional"))
    )
    (net (code "12") (name "EPD_CS") (class "Default")
      (node (ref "J1") (pin "12") (pinfunction "12_12") (pintype "bidirectional"))
      (node (ref "U1") (pin "P$K2") (pinfunction "P0.05/AIN3_P$K2") (pintype "bidirectional"))
    )
    (net (code "13") (name "EPD_DC") (class "Default")
      (node (ref "J1") (pin "11") (pinfunction "11_11") (pintype "bidirectional"))
      (node (ref "U1") (pin "P$AD10") (pinfunction "P0.15_P$AD10") (pintype "bidirectional"))
    )
    (net (code "14") (name "EPD_RST") (class "Default")
      (node (ref "J1") (pin "10") (pinfunction "10_10") (pintype "bidirectional"))
      (node (ref "U1") (pin "P$AC11") (pinfunction "P0.16_P$AC11") (pintype "bidirectional"))
    )
    (net (code "15") (name "GDR") (class "Default")
      (node (ref "J1") (pin "2") (pinfunction "2_2") (pintype "bidirectional"))
      (node (ref "Q3") (pin "1") (pinfunction "G_1") (pintype "bidirectional"))
      (node (ref "R2_EP_DR1") (pin "2") (pinfunction "2_2") (pintype "bidirectional"))
    )
    (net (code "16") (name "GND") (class "Default")
      (node (ref "C1") (pin "2") (pinfunction "2_2") (pintype "passive"))
      (node (ref "C1-EP-DR") (pin "2") (pinfunction "2_2") (pintype "passive"))
      (node (ref "C10") (pin "2") (pinfunction "2_2") (pintype "passive"))
      (node (ref "C11") (pin "2") (pinfunction "2_2") (pintype "passive"))
      (node (ref "C12") (pin "2") (pinfunction "2_2") (pintype "passive"))
      (node (ref "C13") (pin "2") (pinfunction "2_2") (pintype "passive"))
      (node (ref "C14") (pin "2") (pinfunction "2_2") (pintype "passive"))
      (node (ref "C15") (pin "2") (pinfunction "2_2") (pintype "passive"))
      (node (ref "C16") (pin "2") (pinfunction "2_2") (pintype "passive"))
      (node (ref "C17") (pin "1") (pinfunction "1_1") (pintype "passive"))
      (node (ref "C18") (pin "1") (pinfunction "1_1") (pintype "passive"))
      (node (ref "C19") (pin "2") (pinfunction "2_2") (pintype "passive"))
      (node (ref "C2") (pin "2") (pinfunction "2_2") (pintype "passive"))
      (node (ref "C20") (pin "2") (pinfunction "2_2") (pintype "passive"))
      (node (ref "C21") (pin "2") (pinfunction "2_2") (pintype "passive"))
      (node (ref "C22") (pin "2") (pinfunction "2_2") (pintype "passive"))
      (node (ref "C23") (pin "1") (pinfunction "1_1") (pintype "passive"))
      (node (ref "C24") (pin "1") (pinfunction "1_1") (pintype "passive"))
      (node (ref "C25") (pin "2") (pinfunction "2_2") (pintype "passive"))
      (node (ref "C27") (pin "1") (pinfunction "1_1") (pintype "passive"))
      (node (ref "C29") (pin "1") (pinfunction "1_1") (pintype "passive"))
      (node (ref "C3") (pin "2") (pinfunction "2_2") (pintype "passive"))
      (node (ref "C30") (pin "1") (pinfunction "1_1") (pintype "passive"))
      (node (ref "C31") (pin "1") (pinfunction "1_1") (pintype "passive"))
      (node (ref "C32") (pin "1") (pinfunction "1_1") (pintype "passive"))
      (node (ref "C33") (pin "2") (pinfunction "2_2") (pintype "passive"))
      (node (ref "C34") (pin "1") (pinfunction "1_1") (pintype "passive"))
      (node (ref "C37") (pin "1") (pinfunction "1_1") (pintype "passive"))
      (node (ref "C38") (pin "1") (pinfunction "1_1") (pintype "passive"))
      (node (ref "C39") (pin "2") (pinfunction "2_2") (pintype "passive"))
      (node (ref "C4") (pin "2") (pinfunction "2_2") (pintype "passive"))
      (node (ref "C42") (pin "1") (pinfunction "1_1") (pintype "passive"))
      (node (ref "C43") (pin "2") (pinfunction "2_2") (pintype "passive"))
      (node (ref "C5") (pin "2") (pinfunction "2_2") (pintype "passive"))
      (node (ref "C6") (pin "2") (pinfunction "2_2") (pintype "passive"))
      (node (ref "C7") (pin "2") (pinfunction "2_2") (pintype "passive"))
      (node (ref "C8") (pin "2") (pinfunction "2_2") (pintype "passive"))
      (node (ref "C9") (pin "2") (pinfunction "2_2") (pintype "passive"))
      (node (ref "D3") (pin "2") (pinfunction "GND_2") (pintype "bidirectional"))
      (node (ref "D4") (pin "1") (pinfunction "K_1") (pintype "bidirectional"))
      (node (ref "EPD_C1") (pin "1") (pinfunction "1_1") (pintype "passive"))
      (node (ref "EPD_C10") (pin "1") (pinfunction "1_1") (pintype "passive"))
      (node (ref "EPD_C11") (pin "1") (pinfunction "1_1") (pintype "passive"))
      (node (ref "EPD_C12") (pin "1") (pinfunction "1_1") (pintype "passive"))
      (node (ref "EPD_C2") (pin "1") (pinfunction "1_1") (pintype "passive"))
      (node (ref "EPD_C5") (pin "1") (pinfunction "1_1") (pintype "passive"))
      (node (ref "EPD_C6") (pin "1") (pinfunction "1_1") (pintype "passive"))
      (node (ref "EPD_C7") (pin "1") (pinfunction "1_1") (pintype "passive"))
      (node (ref "EPD_C8") (pin "1") (pinfunction "1_1") (pintype "passive"))
      (node (ref "EPD_C9") (pin "1") (pinfunction "1_1") (pintype "passive"))
      (node (ref "IC1") (pin "D2") (pinfunction "GND_D2") (pintype "bidirectional"))
      (node (ref "IC2") (pin "B1") (pinfunction "IN/TRIG_B1") (pintype "bidirectional"))
      (node (ref "IC2") (pin "B3") (pinfunction "GND_B3") (pintype "bidirectional"))
      (node (ref "IC3") (pin "8") (pinfunction "GNDIO_8") (pintype "bidirectional"))
      (node (ref "IC3") (pin "9") (pinfunction "GND_9") (pintype "bidirectional"))
      (node (ref "IC9") (pin "B1") (pinfunction "VSEL_B1") (pintype "bidirectional"))
      (node (ref "IC9") (pin "C1") (pinfunction "AGND_C1") (pintype "bidirectional"))
      (node (ref "IC9") (pin "C2") (pinfunction "PGND_1_C2") (pintype "bidirectional"))
      (node (ref "IC9") (pin "C3") (pinfunction "PGND_2_C3") (pintype "bidirectional"))
      (node (ref "J1") (pin "17") (pinfunction "17_17") (pintype "bidirectional"))
      (node (ref "J1") (pin "8") (pinfunction "8_8") (pintype "bidirectional"))
      (node (ref "J1") (pin "MP1") (pinfunction "MP1_MP1") (pintype "bidirectional"))
      (node (ref "J1") (pin "MP2") (pinfunction "MP2_MP2") (pintype "bidirectional"))
      (node (ref "J2") (pin "3") (pinfunction "3_3") (pintype "bidirectional"))
      (node (ref "J2") (pin "5") (pinfunction "5_5") (pintype "bidirectional"))
      (node (ref "J4") (pin "A12_B1") (pinfunction "GND_A12_B1") (pintype "power_in"))
      (node (ref "J4") (pin "A1_B12") (pinfunction "GND_A1_B12") (pintype "power_in"))
      (node (ref "J4") (pin "SH1") (pinfunction "SHIELD_SH1") (pintype "passive"))
      (node (ref "J4") (pin "SH2") (pinfunction "SHIELD_SH2") (pintype "passive"))
      (node (ref "J4") (pin "SH3") (pinfunction "SHIELD_SH3") (pintype "passive"))
      (node (ref "J4") (pin "SH4") (pinfunction "SHIELD_SH4") (pintype "passive"))
      (node (ref "R1_USB") (pin "1") (pinfunction "1_1") (pintype "bidirectional"))
      (node (ref "R2_EP_DR1") (pin "1") (pinfunction "1_1") (pintype "bidirectional"))
      (node (ref "R2_USB") (pin "2") (pinfunction "2_2") (pintype "bidirectional"))
      (node (ref "R3") (pin "1") (pinfunction "1_1") (pintype "bidirectional"))
      (node (ref "R9") (pin "1") (pinfunction "1_1") (pintype "bidirectional"))
      (node (ref "R_TYPE_SEL") (pin "1") (pinfunction "1_1") (pintype "bidirectional"))
      (node (ref "SJ1") (pin "1") (pinfunction "1_1") (pintype "passive"))
      (node (ref "SW_DN") (pin "1") (pinfunction "1_1") (pintype "passive"))
      (node (ref "SW_ENT") (pin "1") (pinfunction "1_1") (pintype "passive"))
      (node (ref "SW_UP") (pin "1") (pinfunction "1_1") (pintype "passive"))
      (node (ref "TP_BAT_GND") (pin "TP") (pinfunction "TP_TP") (pintype "input"))
      (node (ref "TP_GND") (pin "TP") (pinfunction "TP_TP") (pintype "input"))
      (node (ref "U1") (pin "P$74") (pinfunction "VSS_PAD_P$74") (pintype "bidirectional"))
      (node (ref "U1") (pin "P$75") (pinfunction "VSS_PAD_P$75") (pintype "bidirectional"))
      (node (ref "U1") (pin "P$76") (pinfunction "VSS_PAD_P$76") (pintype "bidirectional"))
      (node (ref "U1") (pin "P$77") (pinfunction "VSS_PAD_P$77") (pintype "bidirectional"))
      (node (ref "U1") (pin "P$78") (pinfunction "VSS_PAD_P$78") (pintype "bidirectional"))
      (node (ref "U1") (pin "P$79") (pinfunction "VSS_PAD_P$79") (pintype "bidirectional"))
      (node (ref "U1") (pin "P$80") (pinfunction "VSS_PAD_P$80") (pintype "bidirectional"))
      (node (ref "U1") (pin "P$81") (pinfunction "VSS_PAD_P$81") (pintype "bidirectional"))
      (node (ref "U1") (pin "P$82") (pinfunction "VSS_PAD_P$82") (pintype "bidirectional"))
      (node (ref "U1") (pin "P$83") (pinfunction "VSS_PAD_P$83") (pintype "bidirectional"))
      (node (ref "U1") (pin "P$84") (pinfunction "VSS_PAD_P$84") (pintype "bidirectional"))
      (node (ref "U1") (pin "P$85") (pinfunction "VSS_PAD_P$85") (pintype "bidirectional"))
      (node (ref "U1") (pin "P$86") (pinfunction "VSS_PAD_P$86") (pintype "bidirectional"))
      (node (ref "U1") (pin "P$87") (pinfunction "VSS_PAD_P$87") (pintype "bidirectional"))
      (node (ref "U1") (pin "P$88") (pinfunction "VSS_PAD_P$88") (pintype "bidirectional"))
      (node (ref "U1") (pin "P$89") (pinfunction "VSS_PAD_P$89") (pintype "bidirectional"))
      (node (ref "U1") (pin "P$90") (pinfunction "VSS_PAD_P$90") (pintype "bidirectional"))
      (node (ref "U1") (pin "P$B7") (pinfunction "VSS_P$B7") (pintype "power_in"))
      (node (ref "U1") (pin "P$F23") (pinfunction "VSS_PA_P$F23") (pintype "bidirectional"))
      (node (ref "U3") (pin "1") (pinfunction "CTG_1") (pintype "power_in"))
      (node (ref "U3") (pin "4") (pinfunction "GND_4") (pintype "power_in"))
      (node (ref "U3") (pin "6") (pinfunction "QSTRT_6") (pintype "input"))
      (node (ref "U3") (pin "9") (pinfunction "EP_9") (pintype "power_in"))
      (node (ref "X1") (pin "2") (pinfunction "2_2") (pintype "passive"))
      (node (ref "X1") (pin "4") (pinfunction "4_4") (pintype "passive"))
    )
    (net (code "17") (name "HAPTIC_EN") (class "Default")
      (node (ref "IC2") (pin "A1") (pinfunction "EN_A1") (pintype "bidirectional"))
      (node (ref "U1") (pin "P$U1") (pinfunction "P0.12_P$U1") (pintype "bidirectional"))
    )
    (net (code "18") (name "IMU_INT1") (class "Default")
      (node (ref "IC3") (pin "5") (pinfunction "INT1_5") (pintype "bidirectional"))
      (node (ref "U1") (pin "P$N1") (pinfunction "P0.08_P$N1") (pintype "bidirectional"))
    )
    (net (code "19") (name "IMU_INT2") (class "Default")
      (node (ref "IC3") (pin "6") (pinfunction "INT2_6") (pintype "bidirectional"))
      (node (ref "U1") (pin "P$P2") (pinfunction "P1.08_P$P2") (pintype "bidirectional"))
    )
    (net (code "20") (name "LX1") (class "Default")
      (node (ref "IC9") (pin "B2") (pinfunction "SW1_1_B2") (pintype "bidirectional"))
      (node (ref "IC9") (pin "B3") (pinfunction "SW1_2_B3") (pintype "bidirectional"))
      (node (ref "L7") (pin "1") (pinfunction "1_1") (pintype "bidirectional"))
    )
    (net (code "21") (name "LX2") (class "Default")
      (node (ref "IC9") (pin "D2") (pinfunction "SW2_1_D2") (pintype "bidirectional"))
      (node (ref "IC9") (pin "D3") (pinfunction "SW2_2_D3") (pintype "bidirectional"))
      (node (ref "L7") (pin "2") (pinfunction "2_2") (pintype "bidirectional"))
    )
    (net (code "22") (name "MOSI") (class "Default")
      (node (ref "J1") (pin "14") (pinfunction "14_14") (pintype "bidirectional"))
      (node (ref "U1") (pin "P$B13") (pinfunction "P0.03/AIN1_P$B13") (pintype "bidirectional"))
    )
    (net (code "23") (name "Net-(D2-K)") (class "Default")
      (node (ref "C2-EP-DR") (pin "1") (pinfunction "1_1") (pintype "passive"))
      (node (ref "D2") (pin "1") (pinfunction "K_1") (pintype "bidirectional"))
      (node (ref "D4") (pin "2") (pinfunction "A_2") (pintype "bidirectional"))
      (node (ref "Q3") (pin "3") (pinfunction "D_3") (pintype "bidirectional"))
    )
    (net (code "24") (name "Net-(D5-A)") (class "Default")
      (node (ref "C2-EP-DR") (pin "2") (pinfunction "2_2") (pintype "passive"))
      (node (ref "D5") (pin "2") (pinfunction "A_2") (pintype "bidirectional"))
      (node (ref "L5") (pin "1") (pinfunction "1_1") (pintype "passive"))
    )
    (net (code "25") (name "Net-(EPD_C1-Pad2)") (class "Default")
      (node (ref "EPD_C1") (pin "2") (pinfunction "2_2") (pintype "passive"))
      (node (ref "J1") (pin "5") (pinfunction "5_5") (pintype "bidirectional"))
    )
    (net (code "26") (name "Net-(EPD_C2-Pad2)") (class "Default")
      (node (ref "EPD_C2") (pin "2") (pinfunction "2_2") (pintype "passive"))
      (node (ref "J1") (pin "4") (pinfunction "4_4") (pintype "bidirectional"))
    )
    (net (code "27") (name "Net-(EPD_C6-Pad2)") (class "Default")
      (node (ref "EPD_C6") (pin "2") (pinfunction "2_2") (pintype "passive"))
      (node (ref "J1") (pin "18") (pinfunction "18_18") (pintype "bidirectional"))
    )
    (net (code "28") (name "Net-(EPD_C7-Pad2)") (class "Default")
      (node (ref "EPD_C7") (pin "2") (pinfunction "2_2") (pintype "passive"))
      (node (ref "J1") (pin "19") (pinfunction "19_19") (pintype "bidirectional"))
    )
    (net (code "29") (name "Net-(EPD_C8-Pad2)") (class "Default")
      (node (ref "EPD_C8") (pin "2") (pinfunction "2_2") (pintype "passive"))
      (node (ref "J1") (pin "20") (pinfunction "20_20") (pintype "bidirectional"))
    )
    (net (code "30") (name "Net-(EPD_C10-Pad2)") (class "Default")
      (node (ref "EPD_C10") (pin "2") (pinfunction "2_2") (pintype "passive"))
      (node (ref "J1") (pin "22") (pinfunction "22_22") (pintype "bidirectional"))
    )
    (net (code "31") (name "Net-(EPD_C12-Pad2)") (class "Default")
      (node (ref "EPD_C12") (pin "2") (pinfunction "2_2") (pintype "passive"))
      (node (ref "J1") (pin "24") (pinfunction "24_24") (pintype "bidirectional"))
    )
    (net (code "32") (name "Net-(IC1-TS{slash}MR)") (class "Default")
      (node (ref "IC1") (pin "D1") (pinfunction "TS/MR_D1") (pintype "bidirectional"))
      (node (ref "R9") (pin "2") (pinfunction "2_2") (pintype "bidirectional"))
    )
    (net (code "33") (name "Net-(IC2-REG)") (class "Default")
      (node (ref "C32") (pin "2") (pinfunction "2_2") (pintype "passive"))
      (node (ref "IC2") (pin "A2") (pinfunction "REG_A2") (pintype "bidirectional"))
    )
    (net (code "34") (name "Net-(IC3-SDO)") (class "Default")
      (node (ref "IC3") (pin "1") (pinfunction "SDO_1") (pintype "bidirectional"))
      (node (ref "R3") (pin "2") (pinfunction "2_2") (pintype "bidirectional"))
    )
    (net (code "35") (name "Net-(IC9-SCL)") (class "Default")
      (node (ref "IC9") (pin "D1") (pinfunction "SCL_D1") (pintype "bidirectional"))
      (node (ref "R4") (pin "2") (pinfunction "2_2") (pintype "bidirectional"))
    )
    (net (code "36") (name "Net-(IC9-SDA)") (class "Default")
      (node (ref "IC9") (pin "E1") (pinfunction "SDA_E1") (pintype "bidirectional"))
      (node (ref "R2") (pin "2") (pinfunction "2_2") (pintype "bidirectional"))
    )
    (net (code "37") (name "Net-(J4-CC1)") (class "Default")
      (node (ref "J4") (pin "A5") (pinfunction "CC1_A5") (pintype "bidirectional"))
      (node (ref "R1_USB") (pin "2") (pinfunction "2_2") (pintype "bidirectional"))
    )
    (net (code "38") (name "Net-(J4-CC2)") (class "Default")
      (node (ref "J4") (pin "B5") (pinfunction "CC2_B5") (pintype "bidirectional"))
      (node (ref "R2_USB") (pin "1") (pinfunction "1_1") (pintype "bidirectional"))
    )
    (net (code "39") (name "Net-(L2-Pad2)") (class "Default")
      (node (ref "L2") (pin "2") (pinfunction "2_2") (pintype "passive"))
      (node (ref "L3") (pin "1") (pinfunction "1_1") (pintype "passive"))
    )
    (net (code "40") (name "Net-(R1_EP_DR-Pad1)") (class "Default")
      (node (ref "R1_EP_DR") (pin "1") (pinfunction "1_1") (pintype "bidirectional"))
      (node (ref "R_TYPE_SEL") (pin "2") (pinfunction "2_2") (pintype "bidirectional"))
      (node (ref "SJ1") (pin "2") (pinfunction "2_2") (pintype "passive"))
    )
    (net (code "41") (name "Net-(U1-ANT)") (class "Default")
      (node (ref "C3") (pin "1") (pinfunction "1_1") (pintype "passive"))
      (node (ref "L1") (pin "1") (pinfunction "1_1") (pintype "passive"))
      (node (ref "U1") (pin "P$H23") (pinfunction "ANT_P$H23") (pintype "bidirectional"))
    )
    (net (code "42") (name "Net-(U1-DCC)") (class "Default")
      (node (ref "L2") (pin "1") (pinfunction "1_1") (pintype "passive"))
      (node (ref "U1") (pin "P$B3") (pinfunction "DCC_P$B3") (pintype "output"))
    )
    (net (code "43") (name "Net-(U1-DEC2)") (class "Default")
      (node (ref "C13") (pin "1") (pinfunction "1_1") (pintype "passive"))
      (node (ref "U1") (pin "P$A18") (pinfunction "DEC2_P$A18") (pintype "bidirectional"))
    )
    (net (code "44") (name "Net-(U1-DEC3)") (class "Default")
      (node (ref "C11") (pin "1") (pinfunction "1_1") (pintype "passive"))
      (node (ref "U1") (pin "P$D23") (pinfunction "DEC3_P$D23") (pintype "bidirectional"))
    )
    (net (code "45") (name "Net-(U1-DEC3V3)") (class "Default")
      (node (ref "C20") (pin "1") (pinfunction "1_1") (pintype "passive"))
      (node (ref "U1") (pin "P$AC5") (pinfunction "DEC3V3_P$AC5") (pintype "bidirectional"))
    )
    (net (code "46") (name "Net-(U1-DEC5)") (class "Default")
      (node (ref "C9") (pin "1") (pinfunction "1_1") (pintype "passive"))
      (node (ref "U1") (pin "P$N24") (pinfunction "DEC5_P$N24") (pintype "bidirectional"))
    )
    (net (code "47") (name "Net-(U1-XC1)") (class "Default")
      (node (ref "C1") (pin "1") (pinfunction "1_1") (pintype "passive"))
      (node (ref "U1") (pin "P$B24") (pinfunction "XC1_P$B24") (pintype "input"))
      (node (ref "X1") (pin "1") (pinfunction "1_1") (pintype "passive"))
    )
    (net (code "48") (name "Net-(U1-XC2)") (class "Default")
      (node (ref "C2") (pin "1") (pinfunction "1_1") (pintype "passive"))
      (node (ref "U1") (pin "P$A23") (pinfunction "XC2_P$A23") (pintype "output"))
      (node (ref "X1") (pin "3") (pinfunction "3_3") (pintype "passive"))
    )
    (net (code "49") (name "OUT+") (class "Default")
      (node (ref "IC2") (pin "A3") (pinfunction "OUT+_A3") (pintype "bidirectional"))
      (node (ref "TP_OP") (pin "TP") (pinfunction "TP_TP") (pintype "input"))
    )
    (net (code "50") (name "OUT-") (class "Default")
      (node (ref "IC2") (pin "C3") (pinfunction "OUT-_C3") (pintype "bidirectional"))
      (node (ref "TP_ON") (pin "TP") (pinfunction "TP_TP") (pintype "input"))
    )
    (net (code "51") (name "P0.00{slash}XL1") (class "Default")
      (node (ref "C17") (pin "2") (pinfunction "2_2") (pintype "passive"))
      (node (ref "U1") (pin "P$D2") (pinfunction "P0.00/XL1_P$D2") (pintype "bidirectional"))
      (node (ref "X2") (pin "1") (pinfunction "1_1") (pintype "passive"))
    )
    (net (code "52") (name "P0.01{slash}XL2") (class "Default")
      (node (ref "C18") (pin "2") (pinfunction "2_2") (pintype "passive"))
      (node (ref "U1") (pin "P$F2") (pinfunction "P0.01/XL2_P$F2") (pintype "bidirectional"))
      (node (ref "X2") (pin "2") (pinfunction "2_2") (pintype "passive"))
    )
    (net (code "53") (name "P0.04") (class "Default")
      (node (ref "U1") (pin "P$J1") (pinfunction "P0.04/AIN2_P$J1") (pintype "bidirectional"))
    )
    (net (code "54") (name "P0.09") (class "Default")
      (node (ref "U1") (pin "P$L24") (pinfunction "P0.09/NFC1_P$L24") (pintype "bidirectional"))
    )
    (net (code "55") (name "P0.13") (class "Default")
      (node (ref "C30") (pin "2") (pinfunction "2_2") (pintype "passive"))
      (node (ref "R5") (pin "1") (pinfunction "1_1") (pintype "bidirectional"))
      (node (ref "SW_UP") (pin "2") (pinfunction "2_2") (pintype "passive"))
      (node (ref "U1") (pin "P$AD8") (pinfunction "P0.13_P$AD8") (pintype "bidirectional"))
    )
    (net (code "56") (name "P0.14") (class "Default")
      (node (ref "C31") (pin "2") (pinfunction "2_2") (pintype "passive"))
      (node (ref "R8") (pin "1") (pinfunction "1_1") (pintype "bidirectional"))
      (node (ref "SW_ENT") (pin "2") (pinfunction "2_2") (pintype "passive"))
      (node (ref "U1") (pin "P$AC9") (pinfunction "P0.14_P$AC9") (pintype "bidirectional"))
    )
    (net (code "57") (name "P0.19") (class "Default")
      (node (ref "U1") (pin "P$AC15") (pinfunction "P0.19_P$AC15") (pintype "bidirectional"))
    )
    (net (code "58") (name "P0.20") (class "Default")
      (node (ref "U1") (pin "P$AD16") (pinfunction "P0.20_P$AD16") (pintype "bidirectional"))
    )
    (net (code "59") (name "P0.21") (class "Default")
      (node (ref "U1") (pin "P$AC17") (pinfunction "P0.21_P$AC17") (pintype "bidirectional"))
    )
    (net (code "60") (name "P0.22") (class "Default")
      (node (ref "U1") (pin "P$AD18") (pinfunction "P0.22_P$AD18") (pintype "bidirectional"))
    )
    (net (code "61") (name "P0.23") (class "Default")
      (node (ref "U1") (pin "P$AC19") (pinfunction "P0.23_P$AC19") (pintype "bidirectional"))
    )
    (net (code "62") (name "P0.24") (class "Default")
      (node (ref "U1") (pin "P$AD20") (pinfunction "P0.24_P$AD20") (pintype "bidirectional"))
    )
    (net (code "63") (name "P0.25") (class "Default")
      (node (ref "U1") (pin "P$AC21") (pinfunction "P0.25_P$AC21") (pintype "bidirectional"))
    )
    (net (code "64") (name "P0.26") (class "Default")
      (node (ref "U1") (pin "P$G1") (pinfunction "P0.26_P$G1") (pintype "bidirectional"))
    )
    (net (code "65") (name "P0.27") (class "Default")
      (node (ref "U1") (pin "P$H2") (pinfunction "P0.27_P$H2") (pintype "bidirectional"))
    )
    (net (code "66") (name "P0.28") (class "Default")
      (node (ref "U1") (pin "P$B11") (pinfunction "P0.28/AIN4_P$B11") (pintype "bidirectional"))
    )
    (net (code "67") (name "P0.29") (class "Default")
      (node (ref "U1") (pin "P$A10") (pinfunction "P0.29/AIN5_P$A10") (pintype "bidirectional"))
    )
    (net (code "68") (name "P0.30") (class "Default")
      (node (ref "U1") (pin "P$B9") (pinfunction "P0.30/AIN6_P$B9") (pintype "bidirectional"))
    )
    (net (code "69") (name "P0.31") (class "Default")
      (node (ref "U1") (pin "P$A8") (pinfunction "P0.31/AIN7_P$A8") (pintype "bidirectional"))
    )
    (net (code "70") (name "P1.01") (class "Default")
      (node (ref "Q1") (pin "1") (pinfunction "G_1") (pintype "bidirectional"))
      (node (ref "R_PWR_EPD") (pin "1") (pinfunction "1_1") (pintype "bidirectional"))
      (node (ref "U1") (pin "P$Y23") (pinfunction "P1.01_P$Y23") (pintype "bidirectional"))
    )
    (net (code "71") (name "P1.02") (class "Default")
      (node (ref "C29") (pin "2") (pinfunction "2_2") (pintype "passive"))
      (node (ref "R7") (pin "1") (pinfunction "1_1") (pintype "bidirectional"))
      (node (ref "SW_DN") (pin "2") (pinfunction "2_2") (pintype "passive"))
      (node (ref "U1") (pin "P$W24") (pinfunction "P1.02_P$W24") (pintype "bidirectional"))
    )
    (net (code "72") (name "P1.03") (class "Default")
      (node (ref "U1") (pin "P$V23") (pinfunction "P1.03_P$V23") (pintype "bidirectional"))
    )
    (net (code "73") (name "P1.04") (class "Default")
      (node (ref "U1") (pin "P$U24") (pinfunction "P1.04_P$U24") (pintype "bidirectional"))
    )
    (net (code "74") (name "P1.05") (class "Default")
      (node (ref "U1") (pin "P$T23") (pinfunction "P1.05_P$T23") (pintype "bidirectional"))
    )
    (net (code "75") (name "P1.06") (class "Default")
      (node (ref "U1") (pin "P$R24") (pinfunction "P1.06_P$R24") (pintype "bidirectional"))
    )
    (net (code "76") (name "P1.07") (class "Default")
      (node (ref "U1") (pin "P$P23") (pinfunction "P1.07_P$P23") (pintype "bidirectional"))
    )
    (net (code "77") (name "P1.09") (class "Default")
      (node (ref "U1") (pin "P$R1") (pinfunction "P1.09_P$R1") (pintype "bidirectional"))
    )
    (net (code "78") (name "P1.10") (class "Default")
      (node (ref "U1") (pin "P$A20") (pinfunction "P1.10_P$A20") (pintype "bidirectional"))
    )
    (net (code "79") (name "P1.11") (class "Default")
      (node (ref "U1") (pin "P$B19") (pinfunction "P1.11_P$B19") (pintype "bidirectional"))
    )
    (net (code "80") (name "P1.12") (class "Default")
      (node (ref "U1") (pin "P$B17") (pinfunction "P1.12_P$B17") (pintype "bidirectional"))
    )
    (net (code "81") (name "P1.13") (class "Default")
      (node (ref "U1") (pin "P$A16") (pinfunction "P1.13_P$A16") (pintype "bidirectional"))
    )
    (net (code "82") (name "P1.14") (class "Default")
      (node (ref "U1") (pin "P$B15") (pinfunction "P1.14_P$B15") (pintype "bidirectional"))
    )
    (net (code "83") (name "P1.15") (class "Default")
      (node (ref "U1") (pin "P$A14") (pinfunction "P1.15_P$A14") (pintype "bidirectional"))
    )
    (net (code "84") (name "PMIC_INT") (class "Default")
      (node (ref "IC1") (pin "A1") (pinfunction "~{INT}_A1") (pintype "bidirectional"))
      (node (ref "U1") (pin "P$T2") (pinfunction "P0.11_P$T2") (pintype "bidirectional"))
    )
    (net (code "85") (name "PREVGH") (class "Default")
      (node (ref "D5") (pin "1") (pinfunction "K_1") (pintype "bidirectional"))
      (node (ref "EPD_C9") (pin "2") (pinfunction "2_2") (pintype "passive"))
      (node (ref "J1") (pin "21") (pinfunction "21_21") (pintype "bidirectional"))
    )
    (net (code "86") (name "PREVGL") (class "Default")
      (node (ref "D2") (pin "2") (pinfunction "A_2") (pintype "bidirectional"))
      (node (ref "EPD_C11") (pin "2") (pinfunction "2_2") (pintype "passive"))
      (node (ref "J1") (pin "23") (pinfunction "23_23") (pintype "bidirectional"))
    )
    (net (code "87") (name "RESE") (class "Default")
      (node (ref "J1") (pin "3") (pinfunction "3_3") (pintype "bidirectional"))
      (node (ref "Q3") (pin "2") (pinfunction "S_2") (pintype "bidirectional"))
      (node (ref "R1_EP_DR") (pin "2") (pinfunction "2_2") (pintype "bidirectional"))
    )
    (net (code "88") (name "RESET") (class "Default")
      (node (ref "J2") (pin "6") (pinfunction "6_6") (pintype "bidirectional"))
      (node (ref "TP_RESET") (pin "TP") (pinfunction "TP_TP") (pintype "input"))
      (node (ref "U1") (pin "P$AC13") (pinfunction "P0.18/RESET_P$AC13") (pintype "bidirectional"))
    )
    (net (code "89") (name "RF") (class "Default")
      (node (ref "ANT1") (pin "1") (pinfunction "FEED_1") (pintype "input"))
      (node (ref "C22") (pin "1") (pinfunction "1_1") (pintype "passive"))
      (node (ref "C4") (pin "1") (pinfunction "1_1") (pintype "passive"))
      (node (ref "L1") (pin "2") (pinfunction "2_2") (pintype "passive"))
    )
    (net (code "90") (name "SCK") (class "Default")
      (node (ref "J1") (pin "13") (pinfunction "13_13") (pintype "bidirectional"))
      (node (ref "U1") (pin "P$A12") (pinfunction "P0.02/AIN0_P$A12") (pintype "bidirectional"))
    )
    (net (code "91") (name "SCL") (class "Default")
      (node (ref "IC1") (pin "B1") (pinfunction "SCL_B1") (pintype "bidirectional"))
      (node (ref "IC2") (pin "C1") (pinfunction "SCL_C1") (pintype "bidirectional"))
      (node (ref "IC3") (pin "12") (pinfunction "SCX_12") (pintype "bidirectional"))
      (node (ref "R17") (pin "2") (pinfunction "2_2") (pintype "bidirectional"))
      (node (ref "R4") (pin "1") (pinfunction "1_1") (pintype "bidirectional"))
      (node (ref "TP_SCL") (pin "TP") (pinfunction "TP_TP") (pintype "input"))
      (node (ref "U1") (pin "P$M2") (pinfunction "P0.07_P$M2") (pintype "bidirectional"))
      (node (ref "U3") (pin "7") (pinfunction "SCL_7") (pintype "input"))
    )
    (net (code "92") (name "SDA") (class "Default")
      (node (ref "IC1") (pin "C1") (pinfunction "SDA_C1") (pintype "bidirectional"))
      (node (ref "IC2") (pin "B2") (pinfunction "SDA_B2") (pintype "bidirectional"))
      (node (ref "IC3") (pin "2") (pinfunction "SDX_2") (pintype "bidirectional"))
      (node (ref "R18") (pin "2") (pinfunction "2_2") (pintype "bidirectional"))
      (node (ref "R2") (pin "1") (pinfunction "1_1") (pintype "bidirectional"))
      (node (ref "TP_SDA") (pin "TP") (pinfunction "TP_TP") (pintype "input"))
      (node (ref "U1") (pin "P$L1") (pinfunction "P0.06_P$L1") (pintype "bidirectional"))
      (node (ref "U3") (pin "8") (pinfunction "SDA_8") (pintype "bidirectional"))
    )
    (net (code "93") (name "SWDCLK") (class "Default")
      (node (ref "J2") (pin "4") (pinfunction "4_4") (pintype "bidirectional"))
      (node (ref "TP_SWDCLK") (pin "TP") (pinfunction "TP_TP") (pintype "input"))
      (node (ref "U1") (pin "P$AA24") (pinfunction "SWDCLK_P$AA24") (pintype "input"))
    )
    (net (code "94") (name "SWDIO") (class "Default")
      (node (ref "J2") (pin "2") (pinfunction "2_2") (pintype "bidirectional"))
      (node (ref "TP_SWDIO") (pin "TP") (pinfunction "TP_TP") (pintype "input"))
      (node (ref "U1") (pin "P$AC24") (pinfunction "SWDIO_P$AC24") (pintype "bidirectional"))
    )
    (net (code "95") (name "SWO") (class "Default")
      (node (ref "TP_SWO") (pin "TP") (pinfunction "TP_TP") (pintype "input"))
      (node (ref "U1") (pin "P$AD22") (pinfunction "P1.00_P$AD22") (pintype "bidirectional"))
    )
    (net (code "96") (name "VBAT") (class "Default")
      (node (ref "C27") (pin "2") (pinfunction "2_2") (pintype "passive"))
      (node (ref "C37") (pin "2") (pinfunction "2_2") (pintype "passive"))
      (node (ref "IC1") (pin "C2") (pinfunction "BAT_C2") (pintype "bidirectional"))
      (node (ref "TP_VBAT") (pin "TP") (pinfunction "TP_TP") (pintype "input"))
      (node (ref "U3") (pin "2") (pinfunction "CELL_2") (pintype "power_in"))
      (node (ref "U3") (pin "3") (pinfunction "VDD_3") (pintype "power_in"))
    )
    (net (code "97") (name "VBUS") (class "Default")
      (node (ref "C21") (pin "1") (pinfunction "1_1") (pintype "passive"))
      (node (ref "C38") (pin "2") (pinfunction "2_2") (pintype "passive"))
      (node (ref "C42") (pin "2") (pinfunction "2_2") (pintype "passive"))
      (node (ref "C43") (pin "1") (pinfunction "1_1") (pintype "passive"))
      (node (ref "D3") (pin "5") (pinfunction "VBUS_5") (pintype "bidirectional"))
      (node (ref "IC1") (pin "A2") (pinfunction "IN_A2") (pintype "bidirectional"))
      (node (ref "J4") (pin "A4_B9") (pinfunction "VBUS_A4_B9") (pintype "power_in"))
      (node (ref "J4") (pin "A9_B4") (pinfunction "VBUS_A9_B4") (pintype "power_in"))
      (node (ref "U1") (pin "P$AD2") (pinfunction "VBUS_P$AD2") (pintype "power_in"))
    )
    (net (code "98") (name "VREG") (class "Default")
      (node (ref "C23") (pin "2") (pinfunction "2_2") (pintype "passive"))
      (node (ref "C24") (pin "2") (pinfunction "2_2") (pintype "passive"))
      (node (ref "C39") (pin "1") (pinfunction "1_1") (pintype "passive"))
      (node (ref "IC1") (pin "B2") (pinfunction "SYS_B2") (pintype "bidirectional"))
      (node (ref "IC9") (pin "A1") (pinfunction "EN_A1") (pintype "bidirectional"))
      (node (ref "IC9") (pin "A2") (pinfunction "VIN_1_A2") (pintype "bidirectional"))
      (node (ref "IC9") (pin "A3") (pinfunction "VIN_2_A3") (pintype "bidirectional"))
      (node (ref "TP_VREG") (pin "TP") (pinfunction "TP_TP") (pintype "input"))
    )
    (net (code "99") (name "unconnected-(ANT1-NC-Pad2)") (class "Default")
      (node (ref "ANT1") (pin "2") (pinfunction "NC_2") (pintype "no_connect"))
    )
    (net (code "100") (name "unconnected-(IC3-ASCL-Pad11)") (class "Default")
      (node (ref "IC3") (pin "11") (pinfunction "ASCL_11") (pintype "bidirectional"))
    )
    (net (code "101") (name "unconnected-(IC3-ASDA-Pad4)") (class "Default")
      (node (ref "IC3") (pin "4") (pinfunction "ASDA_4") (pintype "bidirectional"))
    )
    (net (code "102") (name "unconnected-(J1-Pad1)") (class "Default")
      (node (ref "J1") (pin "1") (pinfunction "1_1") (pintype "bidirectional"))
    )
    (net (code "103") (name "unconnected-(J1-Pad6)") (class "Default")
      (node (ref "J1") (pin "6") (pinfunction "6_6") (pintype "bidirectional"))
    )
    (net (code "104") (name "unconnected-(J1-Pad7)") (class "Default")
      (node (ref "J1") (pin "7") (pinfunction "7_7") (pintype "bidirectional"))
    )
    (net (code "105") (name "unconnected-(J4-SBU1-PadA8)") (class "Default")
      (node (ref "J4") (pin "A8") (pinfunction "SBU1_A8") (pintype "bidirectional"))
    )
    (net (code "106") (name "unconnected-(J4-SBU2-PadB8)") (class "Default")
      (node (ref "J4") (pin "B8") (pinfunction "SBU2_B8") (pintype "bidirectional"))
    )
    (net (code "107") (name "unconnected-(U1-DCCH-PadP$AB2)") (class "Default")
      (node (ref "U1") (pin "P$AB2") (pinfunction "DCCH_P$AB2") (pintype "bidirectional"))
    )
  )
)
